# buck_converter.net
KiCad netlist of a schematic drawn in Altium Designer
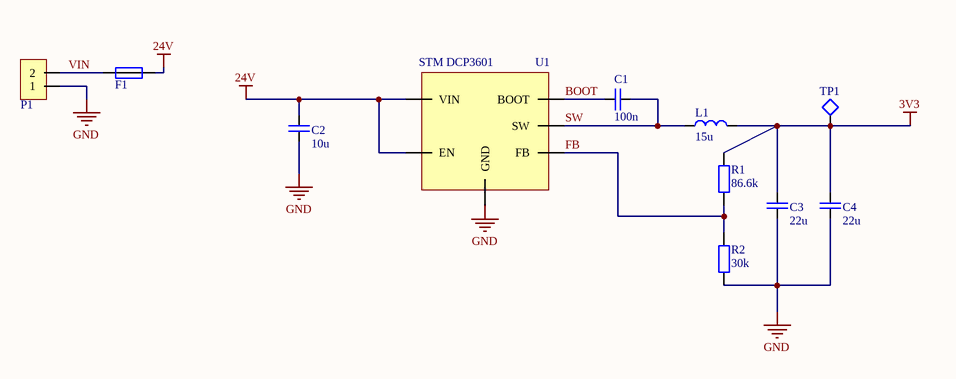
[diagram p0: buck_converter.SchDoc]

(export (version "E")
  (design (tool "Eeschema 10.0.6"))
  (components
    (comp (ref "C1")
      (value "100n")
      (footprint "capacitor_smd_0603")
      (description "Vishay GA0603Y104KXAAC31G")
      (libsource (lib "generic") (part "Capacitor - non-polarised"))
    )
    (comp (ref "C2")
      (value "10u")
      (footprint "capacitor_smd_1206")
      (description "Samsung CL31B106KBHNNNE")
      (libsource (lib "generic") (part "Capacitor - non-polarised"))
    )
    (comp (ref "C3")
      (value "22u")
      (footprint "capacitor_smd_0805")
      (description "TDK C2012X5R1V226M125AC")
      (libsource (lib "generic") (part "Capacitor - non-polarised"))
    )
    (comp (ref "C4")
      (value "22u")
      (footprint "capacitor_smd_0805")
      (description "TDK C2012X5R1V226M125AC")
      (libsource (lib "generic") (part "Capacitor - non-polarised"))
    )
    (comp (ref "F1")
      (value "Fuse")
      (footprint "resisitor_smd_0603")
      (description "Bourns SF-0603HI800M-2")
      (libsource (lib "generic") (part "Fuse"))
    )
    (comp (ref "L1")
      (value "15u")
      (footprint "inductor_smd_5mm8_x_5mm8")
      (description "Bourns SRR5828A-150M")
      (libsource (lib "generic") (part "Inductor"))
    )
    (comp (ref "P1")
      (value "Terminal Block")
      (footprint "terminal_block_1X2_5mm08")
      (description "Adam Tech EBAFA-02-D")
      (libsource (lib "terminal_blocks") (part "Terminal Block 1X2"))
    )
    (comp (ref "R1")
      (value "86.6k")
      (footprint "resisitor_smd_0603")
      (description "Panasonic ERA-3AEB8662V")
      (libsource (lib "generic") (part "Resistor"))
    )
    (comp (ref "R2")
      (value "30k")
      (footprint "resisitor_smd_0603")
      (description "Panasonic ERA-3APB303V")
      (libsource (lib "generic") (part "Resistor"))
    )
    (comp (ref "TP1")
      (value "Test point")
      (footprint "test_point")
      (libsource (lib "generic") (part "Test point"))
    )
    (comp (ref "U1")
      (value "STM DCP3601")
      (footprint "generic_sot23-6L")
      (description "STM DCP3601NDMR")
      (libsource (lib "integrated_circuits") (part "STM DCP3601"))
    )
  )
  (nets
    (net (code "1") (name "/BOOT") (class "Default")
      (node (ref "C1") (pin "2") (pintype "passive"))
      (node (ref "U1") (pin "1") (pinfunction "BOOT_1") (pintype "passive"))
    )
    (net (code "2") (name "/FB") (class "Default")
      (node (ref "R1") (pin "1") (pintype "passive"))
      (node (ref "R2") (pin "1") (pintype "passive"))
      (node (ref "U1") (pin "3") (pinfunction "FB_3") (pintype "passive"))
    )
    (net (code "3") (name "/SW") (class "Default")
      (node (ref "C1") (pin "1") (pintype "passive"))
      (node (ref "L1") (pin "1") (pintype "passive"))
      (node (ref "U1") (pin "6") (pinfunction "SW_6") (pintype "passive"))
    )
    (net (code "4") (name "/VIN") (class "Default")
      (node (ref "F1") (pin "2") (pintype "passive"))
      (node (ref "P1") (pin "2") (pinfunction "2_2") (pintype "passive"))
    )
    (net (code "5") (name "3V3") (class "Default")
      (node (ref "C3") (pin "1") (pintype "passive"))
      (node (ref "C4") (pin "1") (pintype "passive"))
      (node (ref "L1") (pin "2") (pintype "passive"))
      (node (ref "R1") (pin "2") (pintype "passive"))
      (node (ref "TP1") (pin "1") (pintype "passive"))
    )
    (net (code "6") (name "24V") (class "Default")
      (node (ref "C2") (pin "2") (pintype "passive"))
      (node (ref "F1") (pin "1") (pintype "passive"))
      (node (ref "U1") (pin "4") (pinfunction "EN_4") (pintype "passive"))
      (node (ref "U1") (pin "5") (pinfunction "VIN_5") (pintype "passive"))
    )
    (net (code "7") (name "GND") (class "Default")
      (node (ref "C2") (pin "1") (pintype "passive"))
      (node (ref "C3") (pin "2") (pintype "passive"))
      (node (ref "C4") (pin "2") (pintype "passive"))
      (node (ref "P1") (pin "1") (pinfunction "1_1") (pintype "passive"))
      (node (ref "R2") (pin "2") (pintype "passive"))
      (node (ref "U1") (pin "2") (pinfunction "GND_2") (pintype "passive"))
    )
  )
)
